# BiSS.net
KiCad netlist of a schematic drawn in Altium Designer
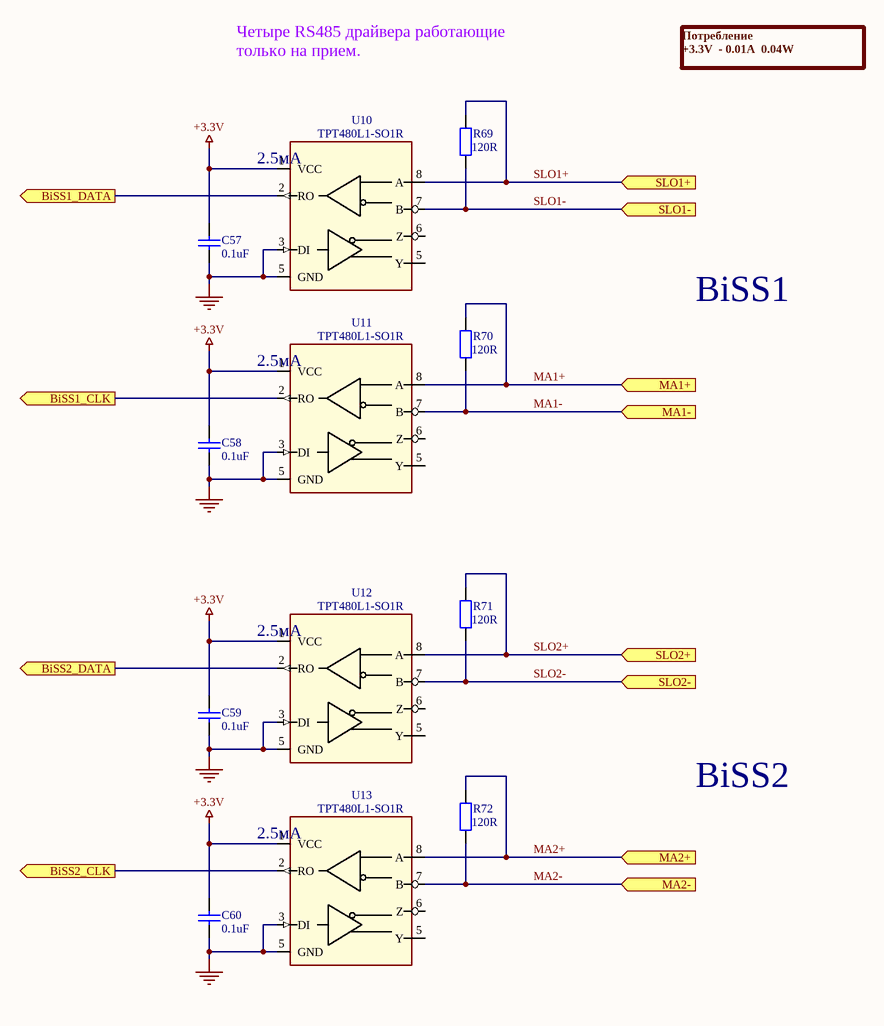
[diagram p0: BiSS.SchDoc]

(export (version "E")
  (design (tool "Eeschema 10.0.6"))
  (components
    (comp (ref "C57")
      (value "0.1uF")
      (footprint "C0402")
      (description "Конденсатор керамический")
      (fields (field (name "VOLTAGE") "25V") (field (name "Comment") "Cap"))
      (libsource (lib "Terra") (part "Cap"))
    )
    (comp (ref "C58")
      (value "0.1uF")
      (footprint "C0402")
      (description "Конденсатор керамический")
      (fields (field (name "VOLTAGE") "25V") (field (name "Comment") "Cap"))
      (libsource (lib "Terra") (part "Cap"))
    )
    (comp (ref "C59")
      (value "0.1uF")
      (footprint "C0402")
      (description "Конденсатор керамический")
      (fields (field (name "VOLTAGE") "25V") (field (name "Comment") "Cap"))
      (libsource (lib "Terra") (part "Cap"))
    )
    (comp (ref "C60")
      (value "0.1uF")
      (footprint "C0402")
      (description "Конденсатор керамический")
      (fields (field (name "VOLTAGE") "25V") (field (name "Comment") "Cap"))
      (libsource (lib "Terra") (part "Cap"))
    )
    (comp (ref "R69")
      (value "120R")
      (footprint "R0402")
      (description "Резистор")
      (fields (field (name "Comment") "Res2"))
      (libsource (lib "Terra") (part "Res2"))
    )
    (comp (ref "R70")
      (value "120R")
      (footprint "R0402")
      (description "Резистор")
      (fields (field (name "Comment") "Res2"))
      (libsource (lib "Terra") (part "Res2"))
    )
    (comp (ref "R71")
      (value "120R")
      (footprint "R0402")
      (description "Резистор")
      (fields (field (name "Comment") "Res2"))
      (libsource (lib "Terra") (part "Res2"))
    )
    (comp (ref "R72")
      (value "120R")
      (footprint "R0402")
      (description "Резистор")
      (fields (field (name "Comment") "Res2"))
      (libsource (lib "Terra") (part "Res2"))
    )
    (comp (ref "U10")
      (value "TPT480L1-SO1R")
      (footprint "SO8")
      (description "RS-485 Transievers")
      (libsource (lib "*") (part "TPT480L1"))
    )
    (comp (ref "U11")
      (value "TPT480L1-SO1R")
      (footprint "SO8")
      (description "RS-485 Transievers")
      (libsource (lib "*") (part "TPT480L1"))
    )
    (comp (ref "U12")
      (value "TPT480L1-SO1R")
      (footprint "SO8")
      (description "RS-485 Transievers")
      (libsource (lib "*") (part "TPT480L1"))
    )
    (comp (ref "U13")
      (value "TPT480L1-SO1R")
      (footprint "SO8")
      (description "RS-485 Transievers")
      (libsource (lib "*") (part "TPT480L1"))
    )
  )
  (nets
    (net (code "1") (name "+3.3V") (class "Default")
      (node (ref "C57") (pin "1") (pinfunction "1_1") (pintype "passive"))
      (node (ref "C58") (pin "1") (pinfunction "1_1") (pintype "passive"))
      (node (ref "C59") (pin "1") (pinfunction "1_1") (pintype "passive"))
      (node (ref "C60") (pin "1") (pinfunction "1_1") (pintype "passive"))
      (node (ref "U10") (pin "1") (pinfunction "VCC_1") (pintype "power_in"))
      (node (ref "U11") (pin "1") (pinfunction "VCC_1") (pintype "power_in"))
      (node (ref "U12") (pin "1") (pinfunction "VCC_1") (pintype "power_in"))
      (node (ref "U13") (pin "1") (pinfunction "VCC_1") (pintype "power_in"))
    )
    (net (code "2") (name "/BiSS1_CLK") (class "Default")
      (node (ref "U11") (pin "2") (pinfunction "RO_2") (pintype "output"))
    )
    (net (code "3") (name "/BiSS1_DATA") (class "Default")
      (node (ref "U10") (pin "2") (pinfunction "RO_2") (pintype "output"))
    )
    (net (code "4") (name "/BiSS2_CLK") (class "Default")
      (node (ref "U13") (pin "2") (pinfunction "RO_2") (pintype "output"))
    )
    (net (code "5") (name "/BiSS2_DATA") (class "Default")
      (node (ref "U12") (pin "2") (pinfunction "RO_2") (pintype "output"))
    )
    (net (code "6") (name "/MA1+") (class "Default")
      (node (ref "R70") (pin "1") (pinfunction "1_1") (pintype "passive"))
      (node (ref "U11") (pin "8") (pinfunction "A_8") (pintype "passive"))
    )
    (net (code "7") (name "/MA1-") (class "Default")
      (node (ref "R70") (pin "2") (pinfunction "2_2") (pintype "passive"))
      (node (ref "U11") (pin "7") (pinfunction "B_7") (pintype "passive"))
    )
    (net (code "8") (name "/MA2+") (class "Default")
      (node (ref "R72") (pin "1") (pinfunction "1_1") (pintype "passive"))
      (node (ref "U13") (pin "8") (pinfunction "A_8") (pintype "passive"))
    )
    (net (code "9") (name "/MA2-") (class "Default")
      (node (ref "R72") (pin "2") (pinfunction "2_2") (pintype "passive"))
      (node (ref "U13") (pin "7") (pinfunction "B_7") (pintype "passive"))
    )
    (net (code "10") (name "/SLO1+") (class "Default")
      (node (ref "R69") (pin "1") (pinfunction "1_1") (pintype "passive"))
      (node (ref "U10") (pin "8") (pinfunction "A_8") (pintype "passive"))
    )
    (net (code "11") (name "/SLO1-") (class "Default")
      (node (ref "R69") (pin "2") (pinfunction "2_2") (pintype "passive"))
      (node (ref "U10") (pin "7") (pinfunction "B_7") (pintype "passive"))
    )
    (net (code "12") (name "/SLO2+") (class "Default")
      (node (ref "R71") (pin "1") (pinfunction "1_1") (pintype "passive"))
      (node (ref "U12") (pin "8") (pinfunction "A_8") (pintype "passive"))
    )
    (net (code "13") (name "/SLO2-") (class "Default")
      (node (ref "R71") (pin "2") (pinfunction "2_2") (pintype "passive"))
      (node (ref "U12") (pin "7") (pinfunction "B_7") (pintype "passive"))
    )
    (net (code "14") (name "GND") (class "Default")
      (node (ref "C57") (pin "2") (pinfunction "2_2") (pintype "passive"))
      (node (ref "C58") (pin "2") (pinfunction "2_2") (pintype "passive"))
      (node (ref "C59") (pin "2") (pinfunction "2_2") (pintype "passive"))
      (node (ref "C60") (pin "2") (pinfunction "2_2") (pintype "passive"))
      (node (ref "U10") (pin "3") (pinfunction "DI_3") (pintype "input"))
      (node (ref "U10") (pin "5") (pinfunction "GND_5") (pintype "power_in"))
      (node (ref "U11") (pin "3") (pinfunction "DI_3") (pintype "input"))
      (node (ref "U11") (pin "5") (pinfunction "GND_5") (pintype "power_in"))
      (node (ref "U12") (pin "3") (pinfunction "DI_3") (pintype "input"))
      (node (ref "U12") (pin "5") (pinfunction "GND_5") (pintype "power_in"))
      (node (ref "U13") (pin "3") (pinfunction "DI_3") (pintype "input"))
      (node (ref "U13") (pin "5") (pinfunction "GND_5") (pintype "power_in"))
    )
    (net (code "15") (name "unconnected-(U10-Y-Pad5)") (class "Default")
      (node (ref "U10") (pin "5") (pinfunction "Y_5") (pintype "passive"))
    )
    (net (code "16") (name "unconnected-(U10-Z-Pad6)") (class "Default")
      (node (ref "U10") (pin "6") (pinfunction "Z_6") (pintype "passive"))
    )
    (net (code "17") (name "unconnected-(U11-Y-Pad5)") (class "Default")
      (node (ref "U11") (pin "5") (pinfunction "Y_5") (pintype "passive"))
    )
    (net (code "18") (name "unconnected-(U11-Z-Pad6)") (class "Default")
      (node (ref "U11") (pin "6") (pinfunction "Z_6") (pintype "passive"))
    )
    (net (code "19") (name "unconnected-(U12-Y-Pad5)") (class "Default")
      (node (ref "U12") (pin "5") (pinfunction "Y_5") (pintype "passive"))
    )
    (net (code "20") (name "unconnected-(U12-Z-Pad6)") (class "Default")
      (node (ref "U12") (pin "6") (pinfunction "Z_6") (pintype "passive"))
    )
    (net (code "21") (name "unconnected-(U13-Y-Pad5)") (class "Default")
      (node (ref "U13") (pin "5") (pinfunction "Y_5") (pintype "passive"))
    )
    (net (code "22") (name "unconnected-(U13-Z-Pad6)") (class "Default")
      (node (ref "U13") (pin "6") (pinfunction "Z_6") (pintype "passive"))
    )
  )
)
